# Power.net
KiCad netlist of a schematic drawn in Altium Designer
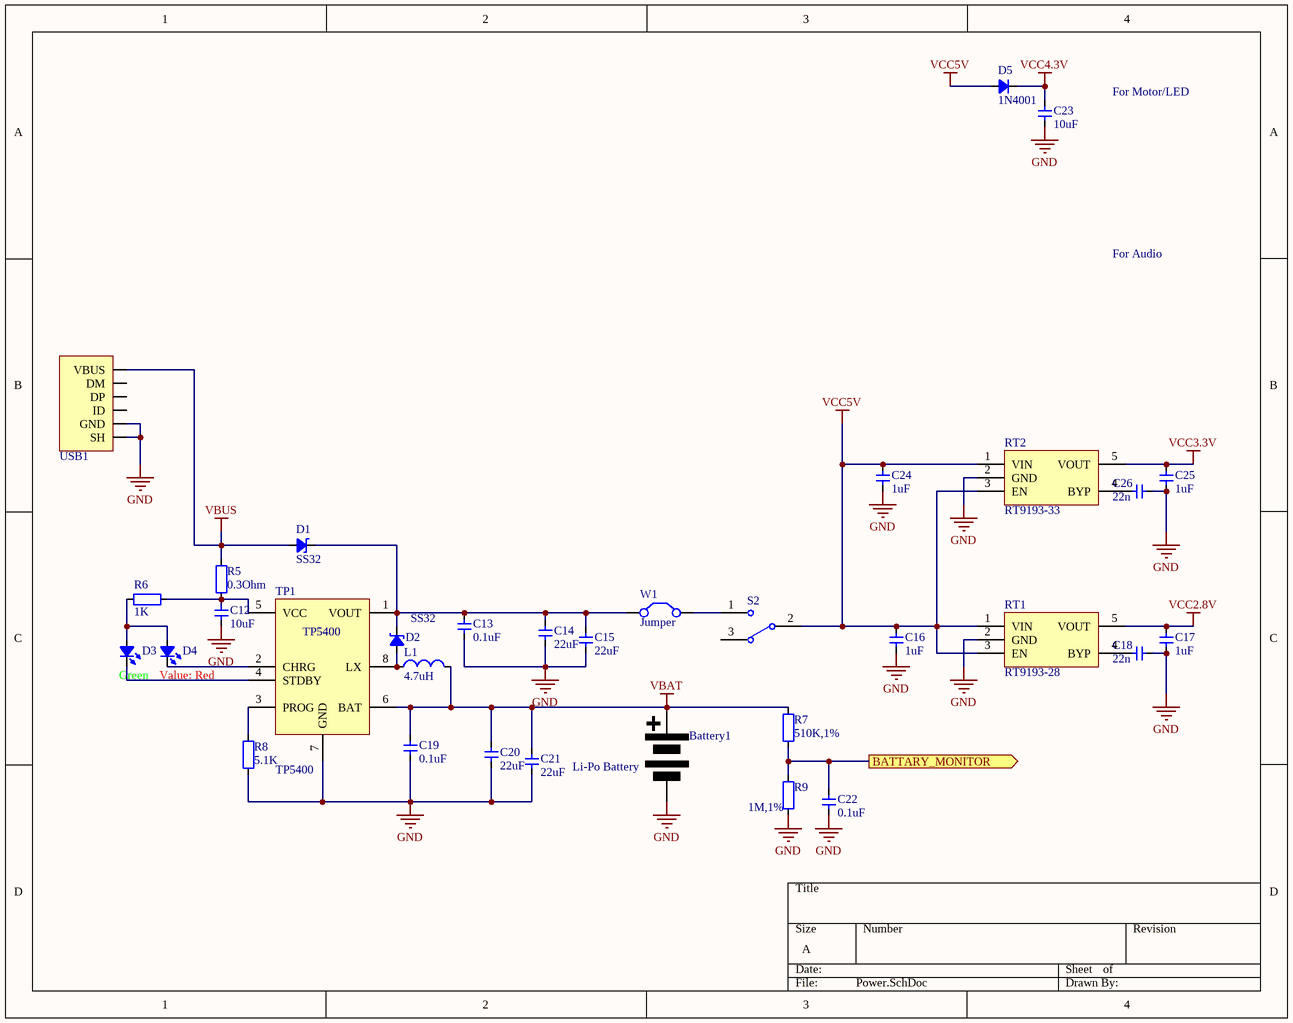
[diagram p0: Power.SchDoc]

(export (version "E")
  (design (tool "Eeschema 10.0.6"))
  (components
    (comp (ref "Battery1")
      (value "Li-Po Battery")
      (footprint "PCB_ConnectorHDR:HDR1X2_2.54_180")
      (description "Li-Po Rechargable Battery")
      (libsource (lib "SCH_Battery") (part "Battery_LiPo"))
    )
    (comp (ref "C12")
      (value "10uF")
      (footprint "PCB_PassiveCap:CAP_0805")
      (description "Capacitor")
      (fields (field (name "Comment") "Cap_0805"))
      (libsource (lib "SCH_Passive") (part "Cap_0805"))
    )
    (comp (ref "C13")
      (value "0.1uF")
      (footprint "PCB_PassiveCap:CAP_0603")
      (description "Capacitor")
      (fields (field (name "Comment") "Cap_0603"))
      (libsource (lib "SCH_Passive") (part "Cap_0603"))
    )
    (comp (ref "C14")
      (value "22uF")
      (footprint "PCB_PassiveCap:CAP_0805")
      (description "Capacitor")
      (fields (field (name "Comment") "Cap_0805"))
      (libsource (lib "SCH_Passive") (part "Cap_0805"))
    )
    (comp (ref "C15")
      (value "22uF")
      (footprint "PCB_PassiveCap:CAP_0805")
      (description "Capacitor")
      (fields (field (name "Comment") "Cap_0805"))
      (libsource (lib "SCH_Passive") (part "Cap_0805"))
    )
    (comp (ref "C16")
      (value "1uF")
      (footprint "PCB_PassiveCap:CAP_0603")
      (description "Capacitor")
      (fields (field (name "Comment") "Cap_0603"))
      (libsource (lib "SCH_Passive") (part "Cap_0603"))
    )
    (comp (ref "C17")
      (value "1uF")
      (footprint "PCB_PassiveCap:CAP_0603")
      (description "Capacitor")
      (fields (field (name "Comment") "Cap_0603"))
      (libsource (lib "SCH_Passive") (part "Cap_0603"))
    )
    (comp (ref "C18")
      (value "22n")
      (footprint "PCB_PassiveCap:CAP_0402")
      (description "Capacitor")
      (fields (field (name "Comment") "Cap_0402"))
      (libsource (lib "SCH_Passive") (part "Cap_0402"))
    )
    (comp (ref "C19")
      (value "0.1uF")
      (footprint "PCB_PassiveCap:CAP_0603")
      (description "Capacitor")
      (fields (field (name "Comment") "Cap_0603"))
      (libsource (lib "SCH_Passive") (part "Cap_0603"))
    )
    (comp (ref "C20")
      (value "22uF")
      (footprint "PCB_PassiveCap:CAP_0805")
      (description "Capacitor")
      (fields (field (name "Comment") "Cap_0805"))
      (libsource (lib "SCH_Passive") (part "Cap_0805"))
    )
    (comp (ref "C21")
      (value "22uF")
      (footprint "PCB_PassiveCap:CAP_0805")
      (description "Capacitor")
      (fields (field (name "Comment") "Cap_0805"))
      (libsource (lib "SCH_Passive") (part "Cap_0805"))
    )
    (comp (ref "C22")
      (value "0.1uF")
      (footprint "PCB_PassiveCap:CAP_0603")
      (description "Capacitor")
      (fields (field (name "Comment") "Cap_0603"))
      (libsource (lib "SCH_Passive") (part "Cap_0603"))
    )
    (comp (ref "C23")
      (value "10uF")
      (footprint "PCB_PassiveCap:CAP_0603")
      (description "Capacitor")
      (fields (field (name "Comment") "Cap_0603"))
      (libsource (lib "SCH_Passive") (part "Cap_0603"))
    )
    (comp (ref "C24")
      (value "1uF")
      (footprint "PCB_PassiveCap:CAP_0603")
      (description "Capacitor")
      (fields (field (name "Comment") "Cap_0603"))
      (libsource (lib "SCH_Passive") (part "Cap_0603"))
    )
    (comp (ref "C25")
      (value "1uF")
      (footprint "PCB_PassiveCap:CAP_0603")
      (description "Capacitor")
      (fields (field (name "Comment") "Cap_0603"))
      (libsource (lib "SCH_Passive") (part "Cap_0603"))
    )
    (comp (ref "C26")
      (value "22n")
      (footprint "PCB_PassiveCap:CAP_0402")
      (description "Capacitor")
      (fields (field (name "Comment") "Cap_0402"))
      (libsource (lib "SCH_Passive") (part "Cap_0402"))
    )
    (comp (ref "D1")
      (value "SS32")
      (footprint "PCB_ActiveDIO:DO-214AC")
      (description "Diode")
      (fields (field (name "Comment") "SchottkyDiode_SOD123"))
      (libsource (lib "SCH_Active") (part "SchottkyDiode_SOD123"))
    )
    (comp (ref "D2")
      (value "SS32")
      (footprint "PCB_ActiveDIO:DO-214AC")
      (description "Diode")
      (fields (field (name "Comment") "SchottkyDiode_SOD123"))
      (libsource (lib "SCH_Active") (part "SchottkyDiode_SOD123"))
    )
    (comp (ref "D3")
      (value "Green")
      (footprint "PCB_ActiveLED:LED_0603_RED")
      (description "LED")
      (fields (field (name "Comment") "Green LED 0603"))
      (libsource (lib "SCH_Active") (part "LED_0603"))
    )
    (comp (ref "D4")
      (value "Red")
      (footprint "PCB_ActiveLED:LED_0603_RED")
      (description "LED")
      (fields (field (name "Comment") "Red LED 0603"))
      (libsource (lib "SCH_Active") (part "LED_0603"))
    )
    (comp (ref "D5")
      (value "1N4001")
      (footprint "PCB_ActiveDIO:DO-214AC")
      (description "Diode")
      (fields (field (name "Comment") "IN4001"))
      (libsource (lib "SCH_Active") (part "Diode_SMA"))
    )
    (comp (ref "L1")
      (value "4.7uH")
      (footprint "PCB_PassiveInd:IND_CD32")
      (description "Inductor")
      (fields (field (name "Comment") "Ind_CD32"))
      (libsource (lib "SCH_Passive") (part "Ind_CD32"))
    )
    (comp (ref "R5")
      (value "0.3Ohm")
      (footprint "PCB_PassiveRes:RES_0603")
      (description "Resistor")
      (fields (field (name "Comment") "Res_0603"))
      (libsource (lib "SCH_Passive") (part "Res_0603"))
    )
    (comp (ref "R6")
      (value "1K")
      (footprint "PCB_PassiveRes:RES_0603")
      (description "Resistor")
      (fields (field (name "Comment") "Res_0603"))
      (libsource (lib "") (part "Res_0603_1"))
    )
    (comp (ref "R7")
      (value "510K,1%")
      (footprint "PCB_PassiveRes:RES_0603")
      (description "Resistor")
      (fields (field (name "Comment") "Res_0603"))
      (libsource (lib "SCH_Passive") (part "Res_0603"))
    )
    (comp (ref "R8")
      (value "5.1K")
      (footprint "PCB_PassiveRes:RES_0603")
      (description "Resistor")
      (fields (field (name "Comment") "Res_0603"))
      (libsource (lib "SCH_Passive") (part "Res_0603"))
    )
    (comp (ref "R9")
      (value "1M,1%")
      (footprint "PCB_PassiveRes:RES_0603")
      (description "Resistor")
      (fields (field (name "Comment") "Res_0603"))
      (libsource (lib "SCH_Passive") (part "Res_0603"))
    )
    (comp (ref "RT1")
      (value "RT9193-28")
      (footprint "PCB_IntegratedCircuit:SOT23-5")
      (description "Power")
      (libsource (lib "SCH_IntegratedCircuit") (part "RT9193"))
    )
    (comp (ref "RT2")
      (value "RT9193-33")
      (footprint "PCB_IntegratedCircuit:SOT23-5")
      (description "Power")
      (libsource (lib "SCH_IntegratedCircuit") (part "RT9193"))
    )
    (comp (ref "S2")
      (value "SwitchSPDT_2.8x6.6_90")
      (footprint "PCB_Switch:SwitchSPDT_2.8X6.6_90")
      (description "Switch")
      (libsource (lib "SCH_Switch") (part "SwitchSPDT_2.8x6.6_90"))
    )
    (comp (ref "TP1")
      (value "TP5400")
      (footprint "PCB_IntegratedCircuit:SOP_E150_8")
      (description "Charge")
      (libsource (lib "SCH_IntegratedCircuit") (part "TP5400"))
    )
    (comp (ref "USB1")
      (value "USB Mini-B")
      (footprint "PCB_USB:USB_Micro-AB")
      (description "USB")
      (libsource (lib "SCH_USB") (part "USB_Micro"))
    )
    (comp (ref "W1")
      (value "Jumper")
      (footprint "HDR1X2")
      (description "Jumper Wire")
      (fields (field (name "PUBLISHER") "Altium Limited"))
      (libsource (lib "Miscellaneous Devices") (part "Jumper"))
    )
  )
  (nets
    (net (code "1") (name "/BATTARY_MONITOR") (class "Default")
      (node (ref "C22") (pin "1") (pinfunction "1_1") (pintype "passive"))
      (node (ref "R7") (pin "1") (pinfunction "1_1") (pintype "passive"))
      (node (ref "R9") (pin "2") (pinfunction "2_2") (pintype "passive"))
    )
    (net (code "2") (name "GND") (class "Default")
      (node (ref "Battery1") (pin "1") (pinfunction "-_1") (pintype "passive"))
      (node (ref "C12") (pin "2") (pinfunction "2_2") (pintype "passive"))
      (node (ref "C13") (pin "1") (pinfunction "1_1") (pintype "passive"))
      (node (ref "C14") (pin "2") (pinfunction "2_2") (pintype "passive"))
      (node (ref "C15") (pin "2") (pinfunction "2_2") (pintype "passive"))
      (node (ref "C16") (pin "2") (pinfunction "2_2") (pintype "passive"))
      (node (ref "C17") (pin "1") (pinfunction "1_1") (pintype "passive"))
      (node (ref "C18") (pin "2") (pinfunction "2_2") (pintype "passive"))
      (node (ref "C19") (pin "1") (pinfunction "1_1") (pintype "passive"))
      (node (ref "C20") (pin "2") (pinfunction "2_2") (pintype "passive"))
      (node (ref "C21") (pin "2") (pinfunction "2_2") (pintype "passive"))
      (node (ref "C22") (pin "2") (pinfunction "2_2") (pintype "passive"))
      (node (ref "C23") (pin "1") (pinfunction "1_1") (pintype "passive"))
      (node (ref "C24") (pin "2") (pinfunction "2_2") (pintype "passive"))
      (node (ref "C25") (pin "1") (pinfunction "1_1") (pintype "passive"))
      (node (ref "C26") (pin "2") (pinfunction "2_2") (pintype "passive"))
      (node (ref "R8") (pin "1") (pinfunction "1_1") (pintype "passive"))
      (node (ref "R9") (pin "1") (pinfunction "1_1") (pintype "passive"))
      (node (ref "RT1") (pin "2") (pinfunction "GND_2") (pintype "passive"))
      (node (ref "RT2") (pin "2") (pinfunction "GND_2") (pintype "passive"))
      (node (ref "TP1") (pin "7") (pinfunction "GND_7") (pintype "passive"))
      (node (ref "USB1") (pin "0") (pinfunction "SH_0") (pintype "passive"))
      (node (ref "USB1") (pin "5") (pinfunction "GND_5") (pintype "passive"))
    )
    (net (code "3") (name "Net-(D1-K)") (class "Default")
      (node (ref "C13") (pin "2") (pinfunction "2_2") (pintype "passive"))
      (node (ref "C14") (pin "1") (pinfunction "1_1") (pintype "passive"))
      (node (ref "C15") (pin "1") (pinfunction "1_1") (pintype "passive"))
      (node (ref "D1") (pin "2") (pinfunction "K_2") (pintype "passive"))
      (node (ref "D2") (pin "2") (pinfunction "K_2") (pintype "passive"))
      (node (ref "TP1") (pin "1") (pinfunction "VOUT_1") (pintype "passive"))
      (node (ref "W1") (pin "1") (pinfunction "C1_1") (pintype "passive"))
    )
    (net (code "4") (name "Net-(D2-A)") (class "Default")
      (node (ref "D2") (pin "1") (pinfunction "A_1") (pintype "passive"))
      (node (ref "L1") (pin "1") (pinfunction "1_1") (pintype "passive"))
      (node (ref "TP1") (pin "8") (pinfunction "LX_8") (pintype "passive"))
    )
    (net (code "5") (name "Net-(D3-A)") (class "Default")
      (node (ref "D3") (pin "1") (pinfunction "A_1") (pintype "passive"))
      (node (ref "D4") (pin "1") (pinfunction "A_1") (pintype "passive"))
      (node (ref "R6") (pin "1") (pinfunction "1_1") (pintype "passive"))
    )
    (net (code "6") (name "Net-(D3-K)") (class "Default")
      (node (ref "D3") (pin "2") (pinfunction "K_2") (pintype "passive"))
      (node (ref "TP1") (pin "4") (pinfunction "STDBY_4") (pintype "passive"))
    )
    (net (code "7") (name "Net-(D4-K)") (class "Default")
      (node (ref "D4") (pin "2") (pinfunction "K_2") (pintype "passive"))
      (node (ref "TP1") (pin "2") (pinfunction "CHRG_2") (pintype "passive"))
    )
    (net (code "8") (name "Net-(RT1-BYP)") (class "Default")
      (node (ref "C18") (pin "1") (pinfunction "1_1") (pintype "passive"))
      (node (ref "RT1") (pin "4") (pinfunction "BYP_4") (pintype "passive"))
    )
    (net (code "9") (name "Net-(RT2-BYP)") (class "Default")
      (node (ref "C26") (pin "1") (pinfunction "1_1") (pintype "passive"))
      (node (ref "RT2") (pin "4") (pinfunction "BYP_4") (pintype "passive"))
    )
    (net (code "10") (name "Net-(TP1-PROG)") (class "Default")
      (node (ref "R8") (pin "2") (pinfunction "2_2") (pintype "passive"))
      (node (ref "TP1") (pin "3") (pinfunction "PROG_3") (pintype "passive"))
    )
    (net (code "11") (name "Net-(TP1-VCC)") (class "Default")
      (node (ref "C12") (pin "1") (pinfunction "1_1") (pintype "passive"))
      (node (ref "R5") (pin "1") (pinfunction "1_1") (pintype "passive"))
      (node (ref "R6") (pin "2") (pinfunction "2_2") (pintype "passive"))
      (node (ref "TP1") (pin "5") (pinfunction "VCC_5") (pintype "passive"))
    )
    (net (code "12") (name "Net-(W1-C2)") (class "Default")
      (node (ref "S2") (pin "1") (pinfunction "1_1") (pintype "passive"))
      (node (ref "W1") (pin "2") (pinfunction "C2_2") (pintype "passive"))
    )
    (net (code "13") (name "VBAT") (class "Default")
      (node (ref "Battery1") (pin "2") (pinfunction "+_2") (pintype "passive"))
      (node (ref "C19") (pin "2") (pinfunction "2_2") (pintype "passive"))
      (node (ref "C20") (pin "1") (pinfunction "1_1") (pintype "passive"))
      (node (ref "C21") (pin "1") (pinfunction "1_1") (pintype "passive"))
      (node (ref "L1") (pin "2") (pinfunction "2_2") (pintype "passive"))
      (node (ref "R7") (pin "2") (pinfunction "2_2") (pintype "passive"))
      (node (ref "TP1") (pin "6") (pinfunction "BAT_6") (pintype "passive"))
    )
    (net (code "14") (name "VBUS") (class "Default")
      (node (ref "D1") (pin "1") (pinfunction "A_1") (pintype "passive"))
      (node (ref "R5") (pin "2") (pinfunction "2_2") (pintype "passive"))
      (node (ref "USB1") (pin "1") (pinfunction "VBUS_1") (pintype "passive"))
    )
    (net (code "15") (name "VCC2.8V") (class "Default")
      (node (ref "C17") (pin "2") (pinfunction "2_2") (pintype "passive"))
      (node (ref "RT1") (pin "5") (pinfunction "VOUT_5") (pintype "passive"))
    )
    (net (code "16") (name "VCC3.3V") (class "Default")
      (node (ref "C25") (pin "2") (pinfunction "2_2") (pintype "passive"))
      (node (ref "RT2") (pin "5") (pinfunction "VOUT_5") (pintype "passive"))
    )
    (net (code "17") (name "VCC4.3V") (class "Default")
      (node (ref "C23") (pin "2") (pinfunction "2_2") (pintype "passive"))
      (node (ref "D5") (pin "2") (pinfunction "K_2") (pintype "passive"))
    )
    (net (code "18") (name "VCC5V") (class "Default")
      (node (ref "C16") (pin "1") (pinfunction "1_1") (pintype "passive"))
      (node (ref "C24") (pin "1") (pinfunction "1_1") (pintype "passive"))
      (node (ref "D5") (pin "1") (pinfunction "A_1") (pintype "passive"))
      (node (ref "RT1") (pin "1") (pinfunction "VIN_1") (pintype "passive"))
      (node (ref "RT1") (pin "3") (pinfunction "EN_3") (pintype "power_in"))
      (node (ref "RT2") (pin "1") (pinfunction "VIN_1") (pintype "passive"))
      (node (ref "RT2") (pin "3") (pinfunction "EN_3") (pintype "power_in"))
      (node (ref "S2") (pin "2") (pinfunction "2_2") (pintype "passive"))
    )
    (net (code "19") (name "unconnected-(S2-Pad3)") (class "Default")
      (node (ref "S2") (pin "3") (pinfunction "3_3") (pintype "passive"))
    )
    (net (code "20") (name "unconnected-(USB1-DM-Pad2)") (class "Default")
      (node (ref "USB1") (pin "2") (pinfunction "DM_2") (pintype "passive"))
    )
    (net (code "21") (name "unconnected-(USB1-DP-Pad3)") (class "Default")
      (node (ref "USB1") (pin "3") (pinfunction "DP_3") (pintype "passive"))
    )
    (net (code "22") (name "unconnected-(USB1-ID-Pad4)") (class "Default")
      (node (ref "USB1") (pin "4") (pinfunction "ID_4") (pintype "passive"))
    )
  )
)
